# IO.net
KiCad netlist of a schematic drawn in Altium Designer
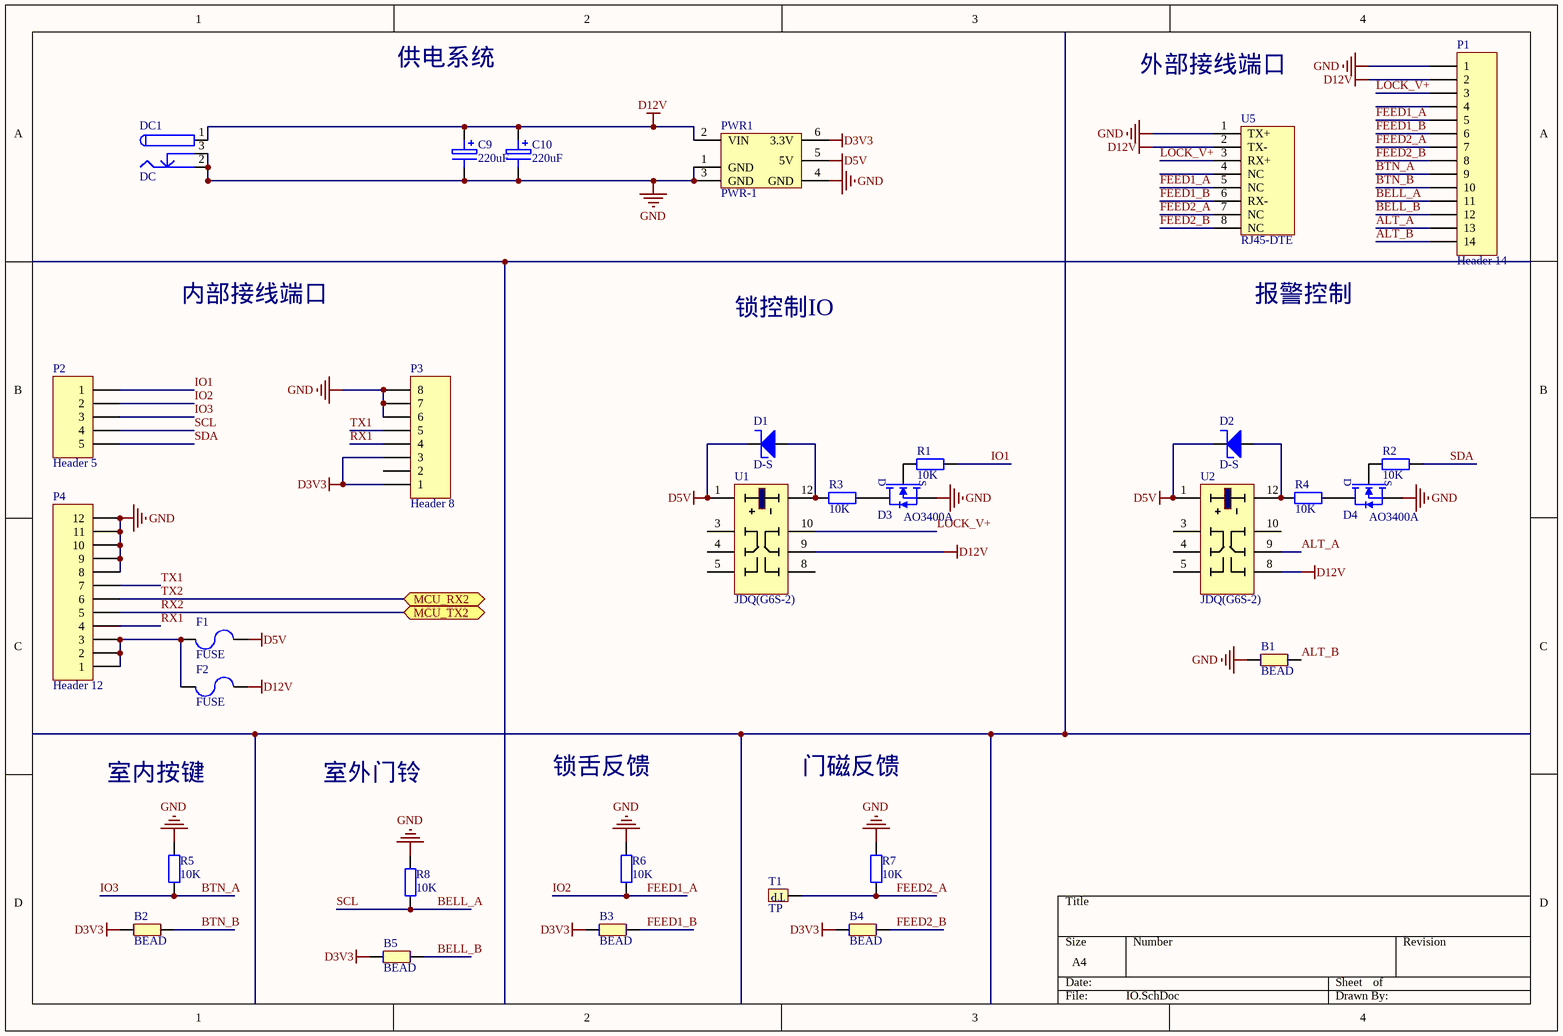
[diagram p0: IO.SchDoc]

(export (version "E")
  (design (tool "Eeschema 10.0.6"))
  (components
    (comp (ref "B1")
      (value "BEAD")
      (footprint "0603L")
      (description "磁珠")
      (libsource (lib "lib_AD") (part "BEAD"))
    )
    (comp (ref "B2")
      (value "BEAD")
      (footprint "0603L")
      (description "磁珠")
      (libsource (lib "lib_AD") (part "BEAD"))
    )
    (comp (ref "B3")
      (value "BEAD")
      (footprint "0603L")
      (description "磁珠")
      (libsource (lib "lib_AD") (part "BEAD"))
    )
    (comp (ref "B4")
      (value "BEAD")
      (footprint "0603L")
      (description "磁珠")
      (libsource (lib "lib_AD") (part "BEAD"))
    )
    (comp (ref "B5")
      (value "BEAD")
      (footprint "0603L")
      (description "磁珠")
      (libsource (lib "lib_AD") (part "BEAD"))
    )
    (comp (ref "C9")
      (value "220uF")
      (footprint "RB.2/.4")
      (description "电解电容")
      (libsource (lib "lib_AD") (part "CAP-E"))
    )
    (comp (ref "C10")
      (value "220uF")
      (footprint "RB.2/.4")
      (description "电解电容")
      (libsource (lib "lib_AD") (part "CAP-E"))
    )
    (comp (ref "D1")
      (value "D-S")
      (footprint "DO-214AC(SMA)")
      (description "肖特基二极管")
      (libsource (lib "lib_AD") (part "D-S"))
    )
    (comp (ref "D2")
      (value "D-S")
      (footprint "DO-214AC(SMA)")
      (description "肖特基二极管")
      (libsource (lib "lib_AD") (part "D-S"))
    )
    (comp (ref "D3")
      (value "AO3400A")
      (footprint "SOT23A")
      (description "NMOS")
      (libsource (lib "lib_AD") (part "MOS-N"))
    )
    (comp (ref "D4")
      (value "AO3400A")
      (footprint "SOT23A")
      (description "NMOS")
      (libsource (lib "lib_AD") (part "MOS-N"))
    )
    (comp (ref "DC1")
      (value "DC")
      (footprint "DC005")
      (description "圆形电源接口")
      (libsource (lib "lib_AD") (part "DC00X"))
    )
    (comp (ref "F1")
      (value "FUSE")
      (footprint "0805F")
      (description "CR-1812-050A60V")
      (libsource (lib "lib_AD") (part "FUSE"))
    )
    (comp (ref "F2")
      (value "FUSE")
      (footprint "0805F")
      (description "CR-1812-050A60V")
      (libsource (lib "lib_AD") (part "FUSE"))
    )
    (comp (ref "P1")
      (value "Header 14")
      (footprint "KF128-5.08-14")
      (description "Header, 14-Pin")
      (fields (field (name "PUBLISHER") "Altium Limited"))
      (libsource (lib "lib_AD") (part "Header 14"))
    )
    (comp (ref "P2")
      (value "Header 5")
      (footprint "XH2.54-5")
      (description "Header, 5-Pin")
      (fields (field (name "PUBLISHER") "Altium Limited"))
      (libsource (lib "lib_AD") (part "Header 5"))
    )
    (comp (ref "P3")
      (value "Header 8")
      (footprint "FPC/1.25T-6P")
      (description "Header, 8-Pin")
      (fields (field (name "PUBLISHER") "Altium Limited"))
      (libsource (lib "lib_AD") (part "Header 8"))
    )
    (comp (ref "P4")
      (value "Header 12")
      (footprint "FFC/SM1.0-2H10")
      (description "Header, 12-Pin")
      (fields (field (name "PUBLISHER") "Altium Limited"))
      (libsource (lib "lib_AD") (part "Header 12"))
    )
    (comp (ref "PWR1") (value "PWR-1") (footprint "PWR-1") (libsource (lib "lib_AD") (part "PWR-1")))
    (comp (ref "R1")
      (value "10K")
      (footprint "0603R")
      (description "普通电阻")
      (libsource (lib "") (part "RES_1"))
    )
    (comp (ref "R2")
      (value "10K")
      (footprint "0603R")
      (description "普通电阻")
      (libsource (lib "") (part "RES_1"))
    )
    (comp (ref "R3")
      (value "10K")
      (footprint "0603R")
      (description "普通电阻")
      (libsource (lib "") (part "RES_1"))
    )
    (comp (ref "R4")
      (value "10K")
      (footprint "0603R")
      (description "普通电阻")
      (libsource (lib "") (part "RES_1"))
    )
    (comp (ref "R5")
      (value "10K")
      (footprint "0603R")
      (description "普通电阻")
      (libsource (lib "lib_AD") (part "RES"))
    )
    (comp (ref "R6")
      (value "10K")
      (footprint "0603R")
      (description "普通电阻")
      (libsource (lib "lib_AD") (part "RES"))
    )
    (comp (ref "R7")
      (value "10K")
      (footprint "0603R")
      (description "普通电阻")
      (libsource (lib "lib_AD") (part "RES"))
    )
    (comp (ref "R8")
      (value "10K")
      (footprint "0603R")
      (description "普通电阻")
      (libsource (lib "lib_AD") (part "RES"))
    )
    (comp (ref "T1")
      (value "TP")
      (footprint "TP1")
      (description "testpoint")
      (libsource (lib "lib_AD") (part "TP"))
    )
    (comp (ref "U1")
      (value "JDQ(G6S-2)")
      (footprint "JDQ-G6S-2")
      (description "继电器（G6S-2 5VDC）")
      (libsource (lib "lib_AD") (part "JDQ(G6S-2)"))
    )
    (comp (ref "U2")
      (value "JDQ(G6S-2)")
      (footprint "JDQ-G6S-2")
      (description "继电器（G6S-2 5VDC）")
      (libsource (lib "lib_AD") (part "JDQ(G6S-2)"))
    )
    (comp (ref "U5") (value "RJ45-DTE") (footprint "RJ45") (libsource (lib "lib_AD") (part "RJ45-DTE")))
  )
  (nets
    (net (code "1") (name "/ALT_A") (class "Default")
      (node (ref "P1") (pin "13") (pinfunction "13_13") (pintype "passive"))
      (node (ref "U2") (pin "9") (pinfunction "9_9") (pintype "passive"))
    )
    (net (code "2") (name "/ALT_B") (class "Default")
      (node (ref "B1") (pin "2") (pinfunction "2_2") (pintype "passive"))
      (node (ref "P1") (pin "14") (pinfunction "14_14") (pintype "passive"))
    )
    (net (code "3") (name "/BELL_A") (class "Default")
      (node (ref "P1") (pin "11") (pinfunction "11_11") (pintype "passive"))
      (node (ref "P2") (pin "4") (pinfunction "4_4") (pintype "passive"))
      (node (ref "R8") (pin "1") (pinfunction "1_1") (pintype "passive"))
    )
    (net (code "4") (name "/BELL_B") (class "Default")
      (node (ref "B5") (pin "2") (pinfunction "2_2") (pintype "passive"))
      (node (ref "P1") (pin "12") (pinfunction "12_12") (pintype "passive"))
    )
    (net (code "5") (name "/BTN_A") (class "Default")
      (node (ref "P1") (pin "9") (pinfunction "9_9") (pintype "passive"))
      (node (ref "P2") (pin "3") (pinfunction "3_3") (pintype "passive"))
      (node (ref "R5") (pin "1") (pinfunction "1_1") (pintype "passive"))
    )
    (net (code "6") (name "/BTN_B") (class "Default")
      (node (ref "B2") (pin "2") (pinfunction "2_2") (pintype "passive"))
      (node (ref "P1") (pin "10") (pinfunction "10_10") (pintype "passive"))
    )
    (net (code "7") (name "/FEED1_A") (class "Default")
      (node (ref "P1") (pin "5") (pinfunction "5_5") (pintype "passive"))
      (node (ref "P2") (pin "2") (pinfunction "2_2") (pintype "passive"))
      (node (ref "R6") (pin "1") (pinfunction "1_1") (pintype "passive"))
      (node (ref "U5") (pin "5") (pinfunction "NC_5") (pintype "passive"))
    )
    (net (code "8") (name "/FEED1_B") (class "Default")
      (node (ref "B3") (pin "2") (pinfunction "2_2") (pintype "passive"))
      (node (ref "P1") (pin "6") (pinfunction "6_6") (pintype "passive"))
      (node (ref "U5") (pin "6") (pinfunction "RX-_6") (pintype "passive"))
    )
    (net (code "9") (name "/FEED2_A") (class "Default")
      (node (ref "P1") (pin "7") (pinfunction "7_7") (pintype "passive"))
      (node (ref "R7") (pin "1") (pinfunction "1_1") (pintype "passive"))
      (node (ref "T1") (pin "1") (pinfunction "1_1") (pintype "passive"))
      (node (ref "U5") (pin "7") (pinfunction "NC_7") (pintype "passive"))
    )
    (net (code "10") (name "/FEED2_B") (class "Default")
      (node (ref "B4") (pin "2") (pinfunction "2_2") (pintype "passive"))
      (node (ref "P1") (pin "8") (pinfunction "8_8") (pintype "passive"))
      (node (ref "U5") (pin "8") (pinfunction "NC_8") (pintype "passive"))
    )
    (net (code "11") (name "/IO1") (class "Default")
      (node (ref "P2") (pin "1") (pinfunction "1_1") (pintype "passive"))
      (node (ref "R1") (pin "2") (pinfunction "2_2") (pintype "passive"))
    )
    (net (code "12") (name "/LOCK_V+") (class "Default")
      (node (ref "P1") (pin "3") (pinfunction "3_3") (pintype "passive"))
      (node (ref "U1") (pin "10") (pinfunction "10_10") (pintype "passive"))
      (node (ref "U5") (pin "3") (pinfunction "RX+_3") (pintype "passive"))
    )
    (net (code "13") (name "/RX1") (class "Default")
      (node (ref "P3") (pin "4") (pinfunction "4_4") (pintype "passive"))
      (node (ref "P4") (pin "4") (pinfunction "4_4") (pintype "passive"))
    )
    (net (code "14") (name "/RX2") (class "Default")
      (node (ref "P4") (pin "5") (pinfunction "5_5") (pintype "passive"))
    )
    (net (code "15") (name "/SDA") (class "Default")
      (node (ref "P2") (pin "5") (pinfunction "5_5") (pintype "passive"))
      (node (ref "R2") (pin "2") (pinfunction "2_2") (pintype "passive"))
    )
    (net (code "16") (name "/TX1") (class "Default")
      (node (ref "P3") (pin "5") (pinfunction "5_5") (pintype "passive"))
      (node (ref "P4") (pin "7") (pinfunction "7_7") (pintype "passive"))
    )
    (net (code "17") (name "/TX2") (class "Default")
      (node (ref "P4") (pin "6") (pinfunction "6_6") (pintype "passive"))
    )
    (net (code "18") (name "D3V3") (class "Default")
      (node (ref "B2") (pin "1") (pinfunction "1_1") (pintype "passive"))
      (node (ref "B3") (pin "1") (pinfunction "1_1") (pintype "passive"))
      (node (ref "B4") (pin "1") (pinfunction "1_1") (pintype "passive"))
      (node (ref "B5") (pin "1") (pinfunction "1_1") (pintype "passive"))
      (node (ref "P3") (pin "1") (pinfunction "1_1") (pintype "passive"))
      (node (ref "P3") (pin "3") (pinfunction "3_3") (pintype "passive"))
      (node (ref "PWR1") (pin "6") (pinfunction "3.3V_6") (pintype "passive"))
    )
    (net (code "19") (name "D5V") (class "Default")
      (node (ref "D1") (pin "K") (pinfunction "2_K") (pintype "passive"))
      (node (ref "D2") (pin "K") (pinfunction "2_K") (pintype "passive"))
      (node (ref "F1") (pin "1") (pinfunction "1_1") (pintype "passive"))
      (node (ref "PWR1") (pin "5") (pinfunction "5V_5") (pintype "passive"))
      (node (ref "U1") (pin "1") (pinfunction "1_1") (pintype "passive"))
      (node (ref "U2") (pin "1") (pinfunction "1_1") (pintype "passive"))
    )
    (net (code "20") (name "D12V") (class "Default")
      (node (ref "C10") (pin "1") (pinfunction "1_1") (pintype "passive"))
      (node (ref "C9") (pin "1") (pinfunction "1_1") (pintype "passive"))
      (node (ref "DC1") (pin "1") (pinfunction "1_1") (pintype "power_in"))
      (node (ref "F2") (pin "1") (pinfunction "1_1") (pintype "passive"))
      (node (ref "P1") (pin "2") (pinfunction "2_2") (pintype "passive"))
      (node (ref "PWR1") (pin "2") (pinfunction "VIN_2") (pintype "passive"))
      (node (ref "U1") (pin "9") (pinfunction "9_9") (pintype "passive"))
      (node (ref "U2") (pin "8") (pinfunction "8_8") (pintype "passive"))
      (node (ref "U5") (pin "2") (pinfunction "TX-_2") (pintype "passive"))
    )
    (net (code "21") (name "GND") (class "Default")
      (node (ref "B1") (pin "1") (pinfunction "1_1") (pintype "passive"))
      (node (ref "C10") (pin "2") (pinfunction "2_2") (pintype "passive"))
      (node (ref "C9") (pin "2") (pinfunction "2_2") (pintype "passive"))
      (node (ref "D3") (pin "2") (pinfunction "S_2") (pintype "passive"))
      (node (ref "D4") (pin "2") (pinfunction "S_2") (pintype "passive"))
      (node (ref "DC1") (pin "2") (pinfunction "2_2") (pintype "power_in"))
      (node (ref "DC1") (pin "3") (pinfunction "3_3") (pintype "power_in"))
      (node (ref "P1") (pin "1") (pinfunction "1_1") (pintype "passive"))
      (node (ref "P3") (pin "6") (pinfunction "6_6") (pintype "passive"))
      (node (ref "P3") (pin "7") (pinfunction "7_7") (pintype "passive"))
      (node (ref "P3") (pin "8") (pinfunction "8_8") (pintype "passive"))
      (node (ref "P4") (pin "10") (pinfunction "10_10") (pintype "passive"))
      (node (ref "P4") (pin "11") (pinfunction "11_11") (pintype "passive"))
      (node (ref "P4") (pin "12") (pinfunction "12_12") (pintype "passive"))
      (node (ref "P4") (pin "8") (pinfunction "8_8") (pintype "passive"))
      (node (ref "P4") (pin "9") (pinfunction "9_9") (pintype "passive"))
      (node (ref "PWR1") (pin "1") (pinfunction "GND_1") (pintype "passive"))
      (node (ref "PWR1") (pin "3") (pinfunction "GND_3") (pintype "passive"))
      (node (ref "PWR1") (pin "4") (pinfunction "GND_4") (pintype "passive"))
      (node (ref "R5") (pin "2") (pinfunction "2_2") (pintype "passive"))
      (node (ref "R6") (pin "2") (pinfunction "2_2") (pintype "passive"))
      (node (ref "R7") (pin "2") (pinfunction "2_2") (pintype "passive"))
      (node (ref "R8") (pin "2") (pinfunction "2_2") (pintype "passive"))
      (node (ref "U5") (pin "1") (pinfunction "TX+_1") (pintype "passive"))
    )
    (net (code "22") (name "Net-(D1-1)") (class "Default")
      (node (ref "D1") (pin "A") (pinfunction "1_A") (pintype "passive"))
      (node (ref "R3") (pin "1") (pinfunction "1_1") (pintype "passive"))
      (node (ref "U1") (pin "12") (pinfunction "12_12") (pintype "passive"))
    )
    (net (code "23") (name "Net-(D2-1)") (class "Default")
      (node (ref "D2") (pin "A") (pinfunction "1_A") (pintype "passive"))
      (node (ref "R4") (pin "1") (pinfunction "1_1") (pintype "passive"))
      (node (ref "U2") (pin "12") (pinfunction "12_12") (pintype "passive"))
    )
    (net (code "24") (name "Net-(D3-D)") (class "Default")
      (node (ref "D3") (pin "3") (pinfunction "D_3") (pintype "passive"))
      (node (ref "R3") (pin "2") (pinfunction "2_2") (pintype "passive"))
    )
    (net (code "25") (name "Net-(D3-G)") (class "Default")
      (node (ref "D3") (pin "1") (pinfunction "G_1") (pintype "passive"))
      (node (ref "R1") (pin "1") (pinfunction "1_1") (pintype "passive"))
    )
    (net (code "26") (name "Net-(D4-D)") (class "Default")
      (node (ref "D4") (pin "3") (pinfunction "D_3") (pintype "passive"))
      (node (ref "R4") (pin "2") (pinfunction "2_2") (pintype "passive"))
    )
    (net (code "27") (name "Net-(D4-G)") (class "Default")
      (node (ref "D4") (pin "1") (pinfunction "G_1") (pintype "passive"))
      (node (ref "R2") (pin "1") (pinfunction "1_1") (pintype "passive"))
    )
    (net (code "28") (name "Net-(F1-Pad2)") (class "Default")
      (node (ref "F1") (pin "2") (pinfunction "2_2") (pintype "passive"))
      (node (ref "F2") (pin "2") (pinfunction "2_2") (pintype "passive"))
      (node (ref "P4") (pin "1") (pinfunction "1_1") (pintype "passive"))
      (node (ref "P4") (pin "2") (pinfunction "2_2") (pintype "passive"))
      (node (ref "P4") (pin "3") (pinfunction "3_3") (pintype "passive"))
    )
    (net (code "29") (name "unconnected-(P1-Pad4)") (class "Default")
      (node (ref "P1") (pin "4") (pinfunction "4_4") (pintype "passive"))
    )
    (net (code "30") (name "unconnected-(P3-Pad2)") (class "Default")
      (node (ref "P3") (pin "2") (pinfunction "2_2") (pintype "passive"))
    )
    (net (code "31") (name "unconnected-(U1-Pad3)") (class "Default")
      (node (ref "U1") (pin "3") (pinfunction "3_3") (pintype "passive"))
    )
    (net (code "32") (name "unconnected-(U1-Pad4)") (class "Default")
      (node (ref "U1") (pin "4") (pinfunction "4_4") (pintype "passive"))
    )
    (net (code "33") (name "unconnected-(U1-Pad5)") (class "Default")
      (node (ref "U1") (pin "5") (pinfunction "5_5") (pintype "passive"))
    )
    (net (code "34") (name "unconnected-(U1-Pad8)") (class "Default")
      (node (ref "U1") (pin "8") (pinfunction "8_8") (pintype "passive"))
    )
    (net (code "35") (name "unconnected-(U2-Pad3)") (class "Default")
      (node (ref "U2") (pin "3") (pinfunction "3_3") (pintype "passive"))
    )
    (net (code "36") (name "unconnected-(U2-Pad4)") (class "Default")
      (node (ref "U2") (pin "4") (pinfunction "4_4") (pintype "passive"))
    )
    (net (code "37") (name "unconnected-(U2-Pad5)") (class "Default")
      (node (ref "U2") (pin "5") (pinfunction "5_5") (pintype "passive"))
    )
    (net (code "38") (name "unconnected-(U2-Pad10)") (class "Default")
      (node (ref "U2") (pin "10") (pinfunction "10_10") (pintype "passive"))
    )
    (net (code "39") (name "unconnected-(U5-NC-Pad4)") (class "Default")
      (node (ref "U5") (pin "4") (pinfunction "NC_4") (pintype "passive"))
    )
  )
)
